# 1_Power.net
KiCad netlist of a schematic drawn in Altium Designer
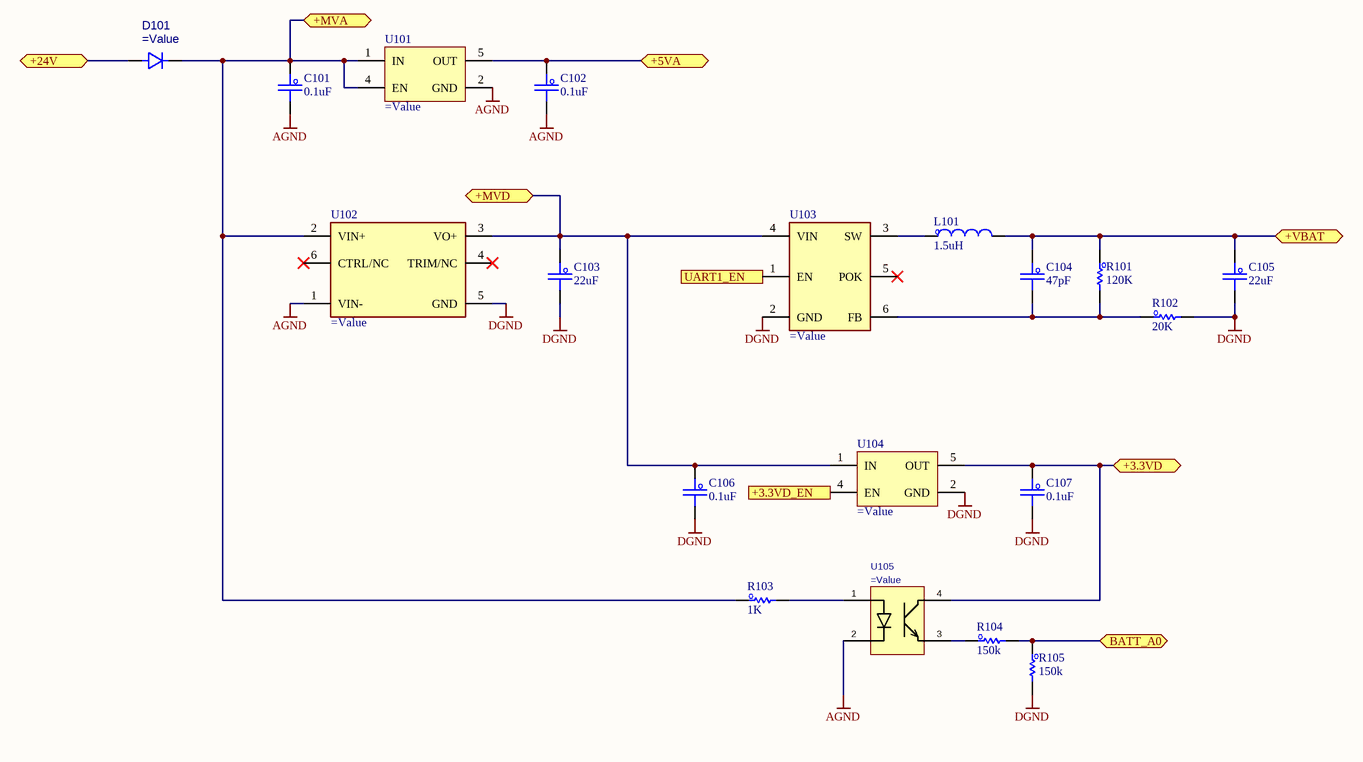
[diagram p0: 1_Power.SchDoc]

(export (version "E")
  (design (tool "Eeschema 10.0.6"))
  (components
    (comp (ref "C101")
      (value "0.1uF")
      (footprint "C_0603")
      (description "CAP CER 0.1UF 50V X7R 0603")
      (fields (field (name "MANUFACTURER") "KEMET") (field (name "PARTNUMBER") "C0603C104K5RACTU"))
      (libsource (lib "UUSymbol") (part "C_Capacitor"))
    )
    (comp (ref "C102")
      (value "0.1uF")
      (footprint "C_0603")
      (description "CAP CER 0.1UF 50V X7R 0603")
      (fields (field (name "MANUFACTURER") "KEMET") (field (name "PARTNUMBER") "C0603C104K5RACTU"))
      (libsource (lib "UUSymbol") (part "C_Capacitor"))
    )
    (comp (ref "C103")
      (value "22uF")
      (footprint "C_0603")
      (description "CAP CER 22UF 10V X5R 0603")
      (fields
        (field (name "MANUFACTURER") "TDK Corporation")
        (field (name "PARTNUMBER") "C1608X5R1A226M080AC")
      )
      (libsource (lib "UUSymbol") (part "C_Capacitor"))
    )
    (comp (ref "C104")
      (value "47pF")
      (footprint "C_0603")
      (description "CAP CER 47PF 50V X7R 0603")
      (fields (field (name "MANUFACTURER") "KEMET") (field (name "PARTNUMBER") "C0603C470J5RAC7867"))
      (libsource (lib "UUSymbol") (part "C_Capacitor"))
    )
    (comp (ref "C105")
      (value "22uF")
      (footprint "C_0603")
      (description "CAP CER 22UF 10V X5R 0603")
      (fields
        (field (name "MANUFACTURER") "TDK Corporation")
        (field (name "PARTNUMBER") "C1608X5R1A226M080AC")
      )
      (libsource (lib "UUSymbol") (part "C_Capacitor"))
    )
    (comp (ref "C106")
      (value "0.1uF")
      (footprint "C_0603")
      (description "CAP CER 0.1UF 50V X7R 0603")
      (fields (field (name "MANUFACTURER") "KEMET") (field (name "PARTNUMBER") "C0603C104K5RACTU"))
      (libsource (lib "UUSymbol") (part "C_Capacitor"))
    )
    (comp (ref "C107")
      (value "0.1uF")
      (footprint "C_0603")
      (description "CAP CER 0.1UF 50V X7R 0603")
      (fields (field (name "MANUFACTURER") "KEMET") (field (name "PARTNUMBER") "C0603C104K5RACTU"))
      (libsource (lib "UUSymbol") (part "C_Capacitor"))
    )
    (comp (ref "D101")
      (value "~")
      (footprint "DFN119P160X30-2M")
      (description "DIODE SCHOTTKY 30V 2A 0603")
      (fields
        (field (name "MANUFACTURER") "Vishay General Semiconductor - Diodes Division")
        (field (name "PARTNUMBER") "VSKY20301608-G4-08")
      )
      (libsource (lib "UUSymbol") (part "D_PW_VSKY20301608"))
    )
    (comp (ref "L101")
      (value "1.5uH")
      (footprint "L_0603")
      (description "1.5 µH Shielded Wirewound Inductor 1 A 200mOhm Max 0603 (1608 Metric)")
      (fields (field (name "MANUFACTURER") "Taiyo Yuden") (field (name "PARTNUMBER") "MBKK1608T1R5M"))
      (libsource (lib "UUSymbol") (part "L_Inductor"))
    )
    (comp (ref "R101")
      (value "120K")
      (footprint "R_0603")
      (description "RES 120K OHM 5% 1/10W 0603")
      (fields (field (name "MANUFACTURER") "YAGEO") (field (name "PARTNUMBER") "RC0603JR-07120KL"))
      (libsource (lib "UUSymbol") (part "R_Resister"))
    )
    (comp (ref "R102")
      (value "20K")
      (footprint "R_0603")
      (description "RES 20K OHM 1% 1/10W 0603")
      (fields (field (name "MANUFACTURER") "YAGEO") (field (name "PARTNUMBER") "RC0603FR-0720KL"))
      (libsource (lib "UUSymbol") (part "R_Resister"))
    )
    (comp (ref "R103")
      (value "1K")
      (footprint "R_0603")
      (description "RES SMD 1K OHM 5% 1/10W 0603")
      (fields (field (name "MANUFACTURER") "Vishay Dale") (field (name "PARTNUMBER") "CRCW06031K00JNEA"))
      (libsource (lib "UUSymbol") (part "R_Resister"))
    )
    (comp (ref "R104")
      (value "150k")
      (footprint "R_0603")
      (description "RES SMD 150K OHM 1% 1/10W 0603")
      (fields (field (name "MANUFACTURER") "Vishay Dale") (field (name "PARTNUMBER") "CRCW0603150KFKEAC"))
      (libsource (lib "UUSymbol") (part "R_Resister"))
    )
    (comp (ref "R105")
      (value "150k")
      (footprint "R_0603")
      (description "RES SMD 150K OHM 1% 1/10W 0603")
      (fields (field (name "MANUFACTURER") "Vishay Dale") (field (name "PARTNUMBER") "CRCW0603150KFKEAC"))
      (libsource (lib "UUSymbol") (part "R_Resister"))
    )
    (comp (ref "U101")
      (value "~")
      (footprint "SOT95P280X145-5N")
      (description "IC REG LINEAR 5V 200MA SOT23-5")
      (fields (field (name "PARTNUMBER") "RT9069-50GB") (field (name "MANUFACTURER") "Richtek Tech"))
      (libsource (lib "UUSymbol") (part "IC_LDO_RT9069-33GB"))
    )
    (comp (ref "U102")
      (value "~")
      (footprint "CONV_HLK-20D2405")
      (description "20W DC/DC IN 9-36V OUT 5V")
      (fields (field (name "MANUFACTURER") "HI-LINK") (field (name "PARTNUMBER") "HLK-10D2405"))
      (libsource (lib "UUSymbol") (part "IC_PMS_HLK-X0D2405"))
    )
    (comp (ref "U103")
      (value "~")
      (footprint "SOT95P270X115-6M")
      (description "DC DC CONVERTER 5V 5W")
      (fields (field (name "PARTNUMBER") "JW5222") (field (name "MANUFACTURER") "JoulWatt Tech"))
      (libsource (lib "UUSymbol") (part "IC_PMS_JW5222"))
    )
    (comp (ref "U104")
      (value "~")
      (footprint "SOT95P280X145-5N")
      (description "200mA 360mV@(10mA) Fixed 3.3V~3.3V Positive 1 36V SOT-23-5 Linear Voltage Regulators (LDO) ROHS")
      (fields (field (name "PARTNUMBER") "RT9069-33GB") (field (name "MANUFACTURER") "Richtek Tech"))
      (libsource (lib "UUSymbol") (part "IC_LDO_RT9069-33GB"))
    )
    (comp (ref "U105")
      (value "~")
      (footprint "SOIC_M618A-3T_VI")
      (description "OPTOISOLATOR 3.75KV TRANS 4-SOP")
      (fields (field (name "MANUFACTURER") "Vishay") (field (name "PARTNUMBER") "VOM618A-3T"))
      (libsource (lib "UUSymbol") (part "IC_OPTO_VOM618A-3T"))
    )
  )
  (nets
    (net (code "1") (name "/+3.3VD") (class "Default")
      (node (ref "C107") (pin "1") (pinfunction "1_1") (pintype "passive"))
      (node (ref "U104") (pin "5") (pinfunction "OUT_5") (pintype "passive"))
      (node (ref "U105") (pin "4") (pinfunction "C_4") (pintype "passive"))
    )
    (net (code "2") (name "/+3.3VD_EN") (class "Default")
      (node (ref "U104") (pin "4") (pinfunction "EN_4") (pintype "passive"))
    )
    (net (code "3") (name "/+5VA") (class "Default")
      (node (ref "C102") (pin "1") (pinfunction "1_1") (pintype "passive"))
      (node (ref "U101") (pin "5") (pinfunction "OUT_5") (pintype "passive"))
    )
    (net (code "4") (name "/+24V") (class "Default")
      (node (ref "D101") (pin "2") (pinfunction "2_2") (pintype "passive"))
    )
    (net (code "5") (name "/+MVA") (class "Default")
      (node (ref "C101") (pin "1") (pinfunction "1_1") (pintype "passive"))
      (node (ref "D101") (pin "1") (pinfunction "1_1") (pintype "passive"))
      (node (ref "R103") (pin "1") (pinfunction "1_1") (pintype "passive"))
      (node (ref "U101") (pin "1") (pinfunction "IN_1") (pintype "passive"))
      (node (ref "U101") (pin "4") (pinfunction "EN_4") (pintype "passive"))
      (node (ref "U102") (pin "2") (pinfunction "VIN+_2") (pintype "passive"))
    )
    (net (code "6") (name "/+MVD") (class "Default")
      (node (ref "C103") (pin "1") (pinfunction "1_1") (pintype "passive"))
      (node (ref "C106") (pin "1") (pinfunction "1_1") (pintype "passive"))
      (node (ref "U102") (pin "3") (pinfunction "VO+_3") (pintype "passive"))
      (node (ref "U103") (pin "4") (pinfunction "VIN_4") (pintype "passive"))
      (node (ref "U104") (pin "1") (pinfunction "IN_1") (pintype "passive"))
    )
    (net (code "7") (name "/+VBAT") (class "Default")
      (node (ref "C104") (pin "1") (pinfunction "1_1") (pintype "passive"))
      (node (ref "C105") (pin "1") (pinfunction "1_1") (pintype "passive"))
      (node (ref "L101") (pin "2") (pinfunction "2_2") (pintype "passive"))
      (node (ref "R101") (pin "1") (pinfunction "1_1") (pintype "passive"))
    )
    (net (code "8") (name "/BATT_A0") (class "Default")
      (node (ref "R104") (pin "2") (pinfunction "2_2") (pintype "passive"))
      (node (ref "R105") (pin "1") (pinfunction "1_1") (pintype "passive"))
    )
    (net (code "9") (name "/UART1_EN") (class "Default")
      (node (ref "U103") (pin "1") (pinfunction "EN_1") (pintype "passive"))
    )
    (net (code "10") (name "AGND") (class "Default")
      (node (ref "C101") (pin "2") (pinfunction "2_2") (pintype "passive"))
      (node (ref "C102") (pin "2") (pinfunction "2_2") (pintype "passive"))
      (node (ref "U101") (pin "2") (pinfunction "GND_2") (pintype "passive"))
      (node (ref "U102") (pin "1") (pinfunction "VIN-_1") (pintype "passive"))
      (node (ref "U105") (pin "2") (pinfunction "C_2_2") (pintype "passive"))
    )
    (net (code "11") (name "DGND") (class "Default")
      (node (ref "C103") (pin "2") (pinfunction "2_2") (pintype "passive"))
      (node (ref "C105") (pin "2") (pinfunction "2_2") (pintype "passive"))
      (node (ref "C106") (pin "2") (pinfunction "2_2") (pintype "passive"))
      (node (ref "C107") (pin "2") (pinfunction "2_2") (pintype "passive"))
      (node (ref "R102") (pin "2") (pinfunction "2_2") (pintype "passive"))
      (node (ref "R105") (pin "2") (pinfunction "2_2") (pintype "passive"))
      (node (ref "U102") (pin "5") (pinfunction "GND_5") (pintype "passive"))
      (node (ref "U103") (pin "2") (pinfunction "GND_2") (pintype "passive"))
      (node (ref "U104") (pin "2") (pinfunction "GND_2") (pintype "passive"))
    )
    (net (code "12") (name "Net-(U103-FB)") (class "Default")
      (node (ref "C104") (pin "2") (pinfunction "2_2") (pintype "passive"))
      (node (ref "R101") (pin "2") (pinfunction "2_2") (pintype "passive"))
      (node (ref "R102") (pin "1") (pinfunction "1_1") (pintype "passive"))
      (node (ref "U103") (pin "6") (pinfunction "FB_6") (pintype "passive"))
    )
    (net (code "13") (name "Net-(U103-SW)") (class "Default")
      (node (ref "L101") (pin "1") (pinfunction "1_1") (pintype "passive"))
      (node (ref "U103") (pin "3") (pinfunction "SW_3") (pintype "passive"))
    )
    (net (code "14") (name "Net-(U105-A)") (class "Default")
      (node (ref "R103") (pin "2") (pinfunction "2_2") (pintype "passive"))
      (node (ref "U105") (pin "1") (pinfunction "A_1") (pintype "passive"))
    )
    (net (code "15") (name "Net-(U105-E)") (class "Default")
      (node (ref "R104") (pin "1") (pinfunction "1_1") (pintype "passive"))
      (node (ref "U105") (pin "3") (pinfunction "E_3") (pintype "passive"))
    )
    (net (code "16") (name "unconnected-(U102-CTRL{slash}NC-Pad6)") (class "Default")
      (node (ref "U102") (pin "6") (pinfunction "CTRL/NC_6") (pintype "passive+no_connect"))
    )
    (net (code "17") (name "unconnected-(U102-TRIM{slash}NC-Pad4)") (class "Default")
      (node (ref "U102") (pin "4") (pinfunction "TRIM/NC_4") (pintype "passive+no_connect"))
    )
    (net (code "18") (name "unconnected-(U103-POK-Pad5)") (class "Default")
      (node (ref "U103") (pin "5") (pinfunction "POK_5") (pintype "passive+no_connect"))
    )
  )
)
